# Sheet1.net
KiCad netlist of a schematic drawn in Altium Designer
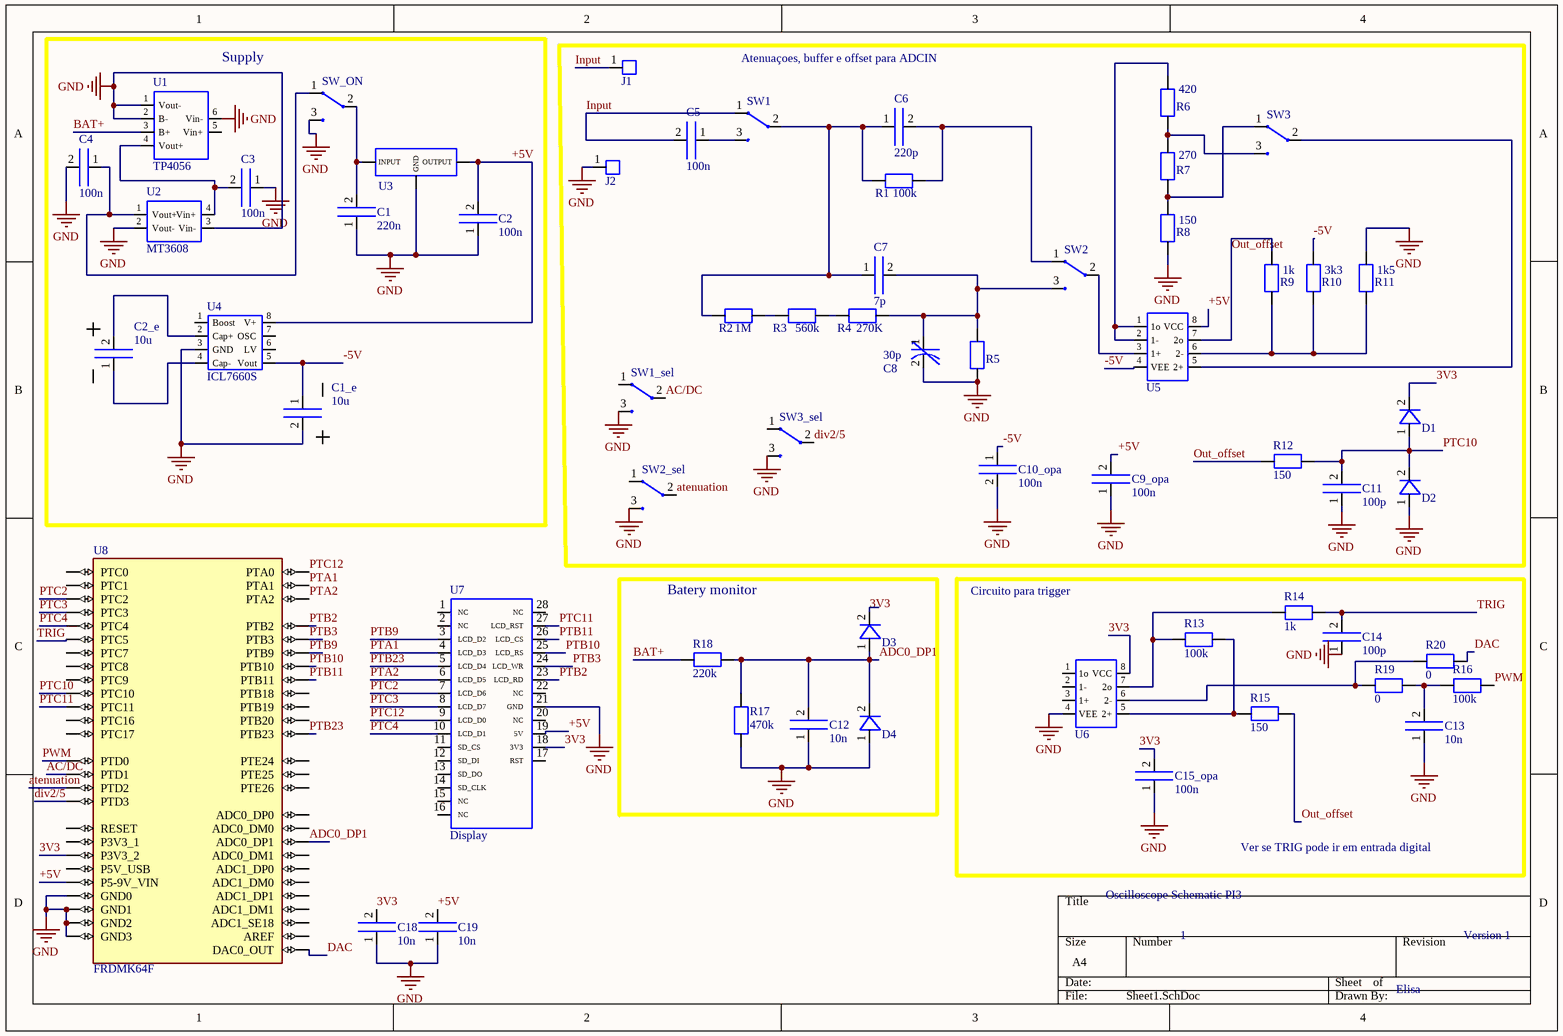
[diagram p0: Sheet1.SchDoc]

(export (version "E")
  (design (tool "Eeschema 10.0.6"))
  (components
    (comp (ref "C1")
      (value "220n")
      (footprint "0805_CAPACITOR")
      (libsource (lib "Schlib2") (part "Capacitor_0805"))
    )
    (comp (ref "C1_e")
      (value "10u")
      (footprint "CAP_THT")
      (description "CAP ALUM 47UF 20% 25V RADIAL TH")
      (libsource (lib "Schlib2") (part "EEU-FC1E470"))
    )
    (comp (ref "C2")
      (value "100n")
      (footprint "0805_CAPACITOR")
      (libsource (lib "Schlib2") (part "Capacitor_0805"))
    )
    (comp (ref "C2_e")
      (value "10u")
      (footprint "CAP_THT")
      (description "CAP ALUM 47UF 20% 25V RADIAL TH")
      (libsource (lib "Schlib2") (part "EEU-FC1E470"))
    )
    (comp (ref "C3")
      (value "100n")
      (footprint "0805_CAPACITOR")
      (libsource (lib "Schlib2") (part "Capacitor_0805"))
    )
    (comp (ref "C4")
      (value "100n")
      (footprint "0805_CAPACITOR")
      (libsource (lib "Schlib2") (part "Capacitor_0805"))
    )
    (comp (ref "C5")
      (value "100n")
      (footprint "0805_CAPACITOR")
      (libsource (lib "Schlib2") (part "Capacitor_0805"))
    )
    (comp (ref "C6")
      (value "220p")
      (footprint "0805_CAPACITOR")
      (libsource (lib "Schlib2") (part "Capacitor_0805"))
    )
    (comp (ref "C7")
      (value "7p")
      (footprint "0805_CAPACITOR")
      (libsource (lib "Schlib2") (part "Capacitor_0805"))
    )
    (comp (ref "C8")
      (value "30p")
      (footprint "CAP_TRIMM_THT")
      (libsource (lib "Schlib2") (part "CAP_TRIMM_THT"))
    )
    (comp (ref "C9_opa")
      (value "100n")
      (footprint "0805_CAPACITOR")
      (libsource (lib "Schlib2") (part "Capacitor_0805"))
    )
    (comp (ref "C10_opa")
      (value "100n")
      (footprint "0805_CAPACITOR")
      (libsource (lib "Schlib2") (part "Capacitor_0805"))
    )
    (comp (ref "C11")
      (value "100p")
      (footprint "0805_CAPACITOR")
      (libsource (lib "Schlib2") (part "Capacitor_0805"))
    )
    (comp (ref "C12")
      (value "10n")
      (footprint "0805_CAPACITOR")
      (libsource (lib "Schlib2") (part "Capacitor_0805"))
    )
    (comp (ref "C13")
      (value "10n")
      (footprint "0805_CAPACITOR")
      (libsource (lib "Schlib2") (part "Capacitor_0805"))
    )
    (comp (ref "C14")
      (value "100p")
      (footprint "0805_CAPACITOR")
      (libsource (lib "Schlib2") (part "Capacitor_0805"))
    )
    (comp (ref "C15_opa")
      (value "100n")
      (footprint "0805_CAPACITOR")
      (libsource (lib "Schlib2") (part "Capacitor_0805"))
    )
    (comp (ref "C18")
      (value "10n")
      (footprint "0805_CAPACITOR")
      (libsource (lib "Schlib2") (part "Capacitor_0805"))
    )
    (comp (ref "C19")
      (value "10n")
      (footprint "0805_CAPACITOR")
      (libsource (lib "Schlib2") (part "Capacitor_0805"))
    )
    (comp (ref "D1") (value "1N4148WT") (footprint "SOD-523") (libsource (lib "Schlib2") (part "1N4148WT")))
    (comp (ref "D2") (value "1N4148WT") (footprint "SOD-523") (libsource (lib "Schlib2") (part "1N4148WT")))
    (comp (ref "D3") (value "1N4148WT") (footprint "SOD-523") (libsource (lib "Schlib2") (part "1N4148WT")))
    (comp (ref "D4") (value "1N4148WT") (footprint "SOD-523") (libsource (lib "Schlib2") (part "1N4148WT")))
    (comp (ref "J1")
      (value "Banana_conector")
      (footprint "Banana_bourne_RED")
      (libsource (lib "Schlib2") (part "Banana_conector"))
    )
    (comp (ref "J2")
      (value "Banana_conector")
      (footprint "Banana_bourne_BLACK")
      (libsource (lib "Schlib2") (part "Banana_conector"))
    )
    (comp (ref "R1")
      (value "100k")
      (footprint "0805_RESISTOR")
      (libsource (lib "Schlib2") (part "0805_resistor"))
    )
    (comp (ref "R2")
      (value "1M")
      (footprint "0805_RESISTOR")
      (libsource (lib "Schlib2") (part "0805_resistor"))
    )
    (comp (ref "R3")
      (value "560k")
      (footprint "0805_RESISTOR")
      (libsource (lib "Schlib2") (part "0805_resistor"))
    )
    (comp (ref "R4")
      (value "270K")
      (footprint "0805_RESISTOR")
      (libsource (lib "Schlib2") (part "0805_resistor"))
    )
    (comp (ref "R5")
      (value "200k")
      (footprint "0805_RESISTOR")
      (libsource (lib "Schlib2") (part "0805_resistor"))
    )
    (comp (ref "R6")
      (value "420")
      (footprint "0805_RESISTOR")
      (libsource (lib "Schlib2") (part "0805_resistor"))
    )
    (comp (ref "R7")
      (value "270")
      (footprint "0805_RESISTOR")
      (libsource (lib "Schlib2") (part "0805_resistor"))
    )
    (comp (ref "R8")
      (value "150")
      (footprint "0805_RESISTOR")
      (libsource (lib "Schlib2") (part "0805_resistor"))
    )
    (comp (ref "R9")
      (value "1k")
      (footprint "0805_RESISTOR")
      (libsource (lib "Schlib2") (part "0805_resistor"))
    )
    (comp (ref "R10")
      (value "3k3")
      (footprint "0805_RESISTOR")
      (libsource (lib "Schlib2") (part "0805_resistor"))
    )
    (comp (ref "R11")
      (value "1k5")
      (footprint "0805_RESISTOR")
      (libsource (lib "Schlib2") (part "0805_resistor"))
    )
    (comp (ref "R12")
      (value "150")
      (footprint "0805_RESISTOR")
      (libsource (lib "Schlib2") (part "0805_resistor"))
    )
    (comp (ref "R13")
      (value "100k")
      (footprint "0805_RESISTOR")
      (libsource (lib "Schlib2") (part "0805_resistor"))
    )
    (comp (ref "R14")
      (value "1k")
      (footprint "0805_RESISTOR")
      (libsource (lib "Schlib2") (part "0805_resistor"))
    )
    (comp (ref "R15")
      (value "150")
      (footprint "0805_RESISTOR")
      (libsource (lib "Schlib2") (part "0805_resistor"))
    )
    (comp (ref "R16")
      (value "100k")
      (footprint "0805_RESISTOR")
      (libsource (lib "Schlib2") (part "0805_resistor"))
    )
    (comp (ref "R17")
      (value "470k")
      (footprint "0805_RESISTOR")
      (libsource (lib "Schlib2") (part "0805_resistor"))
    )
    (comp (ref "R18")
      (value "220k")
      (footprint "0805_RESISTOR")
      (libsource (lib "Schlib2") (part "0805_resistor"))
    )
    (comp (ref "R19")
      (value "0")
      (footprint "0805_RESISTOR")
      (libsource (lib "Schlib2") (part "0805_resistor"))
    )
    (comp (ref "R20")
      (value "0")
      (footprint "0805_RESISTOR")
      (libsource (lib "Schlib2") (part "0805_resistor"))
    )
    (comp (ref "SW1") (value "SW") (footprint "SW") (libsource (lib "Schlib2") (part "SW")))
    (comp (ref "SW1_sel") (value "SW") (footprint "SW") (libsource (lib "Schlib2") (part "SW")))
    (comp (ref "SW2") (value "SW") (footprint "SW") (libsource (lib "Schlib2") (part "SW")))
    (comp (ref "SW2_sel") (value "SW") (footprint "SW") (libsource (lib "Schlib2") (part "SW")))
    (comp (ref "SW3") (value "SW") (footprint "SW") (libsource (lib "Schlib2") (part "SW")))
    (comp (ref "SW3_sel") (value "SW") (footprint "SW") (libsource (lib "Schlib2") (part "SW")))
    (comp (ref "SW_ON") (value "SW") (footprint "SW") (libsource (lib "Schlib2") (part "SW")))
    (comp (ref "U1") (value "TP4056") (footprint "TP0456") (libsource (lib "Schlib2") (part "TP4056")))
    (comp (ref "U2") (value "MT3608") (footprint "MT3608") (libsource (lib "Schlib2") (part "MT3608")))
    (comp (ref "U3")
      (value "L7805")
      (footprint "D2PAK")
      (description "IC REG LINEAR 5V 1.5A")
      (libsource (lib "Schlib2") (part "L7805"))
    )
    (comp (ref "U4") (value "ICL7660S") (footprint "8 -PDIP") (libsource (lib "Schlib2") (part "ICL7660S")))
    (comp (ref "U5") (value "TL082C") (footprint "8-SOIC") (libsource (lib "Schlib2") (part "TL082C")))
    (comp (ref "U6") (value "TL082C") (footprint "8-SOIC") (libsource (lib "Schlib2") (part "TL082C")))
    (comp (ref "U7") (value "Display") (footprint "Display") (libsource (lib "Schlib2") (part "Display")))
    (comp (ref "U8") (value "FRDMK64F") (footprint "FRDMK64F") (libsource (lib "Schlib2") (part "FRDMK64F")))
  )
  (nets
    (net (code "1") (name "/+5V") (class "Default")
      (node (ref "C19") (pin "2") (pinfunction "0_2") (pintype "passive"))
      (node (ref "C2") (pin "2") (pinfunction "0_2") (pintype "passive"))
      (node (ref "C9_opa") (pin "2") (pinfunction "0_2") (pintype "passive"))
      (node (ref "U3") (pin "2") (pinfunction "OUTPUT_2") (pintype "passive"))
      (node (ref "U4") (pin "8") (pinfunction "V+_8") (pintype "passive"))
      (node (ref "U5") (pin "8") (pinfunction "VCC_8") (pintype "passive"))
      (node (ref "U7") (pin "19") (pinfunction "5V_19") (pintype "passive"))
      (node (ref "U8") (pin "J3-16") (pinfunction "P5-9V_VIN_J3-16") (pintype "bidirectional"))
    )
    (net (code "2") (name "/-5V") (class "Default")
      (node (ref "C10_opa") (pin "1") (pinfunction "1_1") (pintype "passive"))
      (node (ref "C1_e") (pin "1") (pinfunction "1_1") (pintype "passive"))
      (node (ref "R10") (pin "2") (pinfunction "2_2") (pintype "passive"))
      (node (ref "U4") (pin "5") (pinfunction "Vout_5") (pintype "passive"))
      (node (ref "U5") (pin "4") (pinfunction "VEE_4") (pintype "passive"))
    )
    (net (code "3") (name "/3V3") (class "Default")
      (node (ref "C15_opa") (pin "2") (pinfunction "0_2") (pintype "passive"))
      (node (ref "C18") (pin "2") (pinfunction "0_2") (pintype "passive"))
      (node (ref "D1") (pin "2") (pintype "passive"))
      (node (ref "D3") (pin "2") (pintype "passive"))
      (node (ref "U6") (pin "8") (pinfunction "VCC_8") (pintype "passive"))
      (node (ref "U7") (pin "18") (pinfunction "3V3_18") (pintype "passive"))
      (node (ref "U8") (pin "J3-8") (pinfunction "P3V3_2_J3-8") (pintype "bidirectional"))
    )
    (net (code "4") (name "/AC{slash}DC") (class "Default")
      (node (ref "SW1_sel") (pin "2") (pinfunction "2_2") (pintype "passive"))
      (node (ref "U8") (pin "J2-12") (pinfunction "PTD1_J2-12") (pintype "bidirectional"))
    )
    (net (code "5") (name "/ADC0_DP1") (class "Default")
      (node (ref "C12") (pin "2") (pinfunction "0_2") (pintype "passive"))
      (node (ref "D3") (pin "1") (pintype "passive"))
      (node (ref "D4") (pin "2") (pintype "passive"))
      (node (ref "R17") (pin "1") (pinfunction "1_1") (pintype "passive"))
      (node (ref "R18") (pin "1") (pinfunction "1_1") (pintype "passive"))
      (node (ref "U8") (pin "J4-1") (pinfunction "ADC0_DP1_J4-1") (pintype "bidirectional"))
    )
    (net (code "6") (name "/BAT+") (class "Default")
      (node (ref "R18") (pin "2") (pinfunction "2_2") (pintype "passive"))
      (node (ref "U1") (pin "3") (pinfunction "B+_3") (pintype "passive"))
    )
    (net (code "7") (name "/DAC") (class "Default")
      (node (ref "R20") (pin "1") (pinfunction "1_1") (pintype "passive"))
      (node (ref "U8") (pin "J4-11") (pinfunction "DAC0_OUT_J4-11") (pintype "bidirectional"))
    )
    (net (code "8") (name "/Input") (class "Default")
      (node (ref "C5") (pin "2") (pinfunction "0_2") (pintype "passive"))
      (node (ref "J1") (pin "1") (pinfunction "1_1") (pintype "passive"))
      (node (ref "SW1") (pin "1") (pinfunction "1_1") (pintype "passive"))
    )
    (net (code "9") (name "/Out_offset") (class "Default")
      (node (ref "R12") (pin "2") (pinfunction "2_2") (pintype "passive"))
      (node (ref "R15") (pin "1") (pinfunction "1_1") (pintype "passive"))
      (node (ref "R9") (pin "2") (pinfunction "2_2") (pintype "passive"))
      (node (ref "U5") (pin "7") (pinfunction "2o_7") (pintype "passive"))
    )
    (net (code "10") (name "/PTA1") (class "Default")
      (node (ref "U7") (pin "4") (pinfunction "LCD_D3_4") (pintype "passive"))
      (node (ref "U8") (pin "J1-8") (pinfunction "PTA1_J1-8") (pintype "bidirectional"))
    )
    (net (code "11") (name "/PTA2") (class "Default")
      (node (ref "U7") (pin "6") (pinfunction "LCD_D5_6") (pintype "passive"))
      (node (ref "U8") (pin "J1-12") (pinfunction "PTA2_J1-12") (pintype "bidirectional"))
    )
    (net (code "12") (name "/PTB2") (class "Default")
      (node (ref "U7") (pin "23") (pinfunction "LCD_RD_23") (pintype "passive"))
      (node (ref "U8") (pin "J4-2") (pinfunction "PTB2_J4-2") (pintype "bidirectional"))
    )
    (net (code "13") (name "/PTB3") (class "Default")
      (node (ref "U7") (pin "24") (pinfunction "LCD_WR_24") (pintype "passive"))
      (node (ref "U8") (pin "J4-4") (pinfunction "PTB3_J4-4") (pintype "bidirectional"))
    )
    (net (code "14") (name "/PTB9") (class "Default")
      (node (ref "U7") (pin "3") (pinfunction "LCD_D2_3") (pintype "passive"))
      (node (ref "U8") (pin "J1-6") (pinfunction "PTB9_J1-6") (pintype "bidirectional"))
    )
    (net (code "15") (name "/PTB10") (class "Default")
      (node (ref "U7") (pin "25") (pinfunction "LCD_RS_25") (pintype "passive"))
      (node (ref "U8") (pin "J4-6") (pinfunction "PTB10_J4-6") (pintype "bidirectional"))
    )
    (net (code "16") (name "/PTB11") (class "Default")
      (node (ref "U7") (pin "26") (pinfunction "LCD_CS_26") (pintype "passive"))
      (node (ref "U8") (pin "J4-8") (pinfunction "PTB11_J4-8") (pintype "bidirectional"))
    )
    (net (code "17") (name "/PTB23") (class "Default")
      (node (ref "U7") (pin "5") (pinfunction "LCD_D4_5") (pintype "passive"))
      (node (ref "U8") (pin "J1-10") (pinfunction "PTB23_J1-10") (pintype "bidirectional"))
    )
    (net (code "18") (name "/PTC2") (class "Default")
      (node (ref "U7") (pin "7") (pinfunction "LCD_D6_7") (pintype "passive"))
      (node (ref "U8") (pin "J1-14") (pinfunction "PTC2_J1-14") (pintype "bidirectional"))
    )
    (net (code "19") (name "/PTC3") (class "Default")
      (node (ref "U7") (pin "8") (pinfunction "LCD_D7_8") (pintype "passive"))
      (node (ref "U8") (pin "J1-16") (pinfunction "PTC3_J1-16") (pintype "bidirectional"))
    )
    (net (code "20") (name "/PTC4") (class "Default")
      (node (ref "U7") (pin "10") (pinfunction "LCD_D1_10") (pintype "passive"))
      (node (ref "U8") (pin "J2-4") (pinfunction "PTC4_J2-4") (pintype "bidirectional"))
    )
    (net (code "21") (name "/PTC10") (class "Default")
      (node (ref "C11") (pin "2") (pinfunction "0_2") (pintype "passive"))
      (node (ref "D1") (pin "1") (pintype "passive"))
      (node (ref "D2") (pin "2") (pintype "passive"))
      (node (ref "R12") (pin "1") (pinfunction "1_1") (pintype "passive"))
      (node (ref "U8") (pin "J4-12") (pinfunction "PTC10_J4-12") (pintype "bidirectional"))
    )
    (net (code "22") (name "/PTC11") (class "Default")
      (node (ref "U7") (pin "27") (pinfunction "LCD_RST_27") (pintype "passive"))
      (node (ref "U8") (pin "J4-10") (pinfunction "PTC11_J4-10") (pintype "bidirectional"))
    )
    (net (code "23") (name "/PTC12") (class "Default")
      (node (ref "U7") (pin "9") (pinfunction "LCD_D0_9") (pintype "passive"))
      (node (ref "U8") (pin "J2-2") (pinfunction "PTA0_J2-2") (pintype "bidirectional"))
    )
    (net (code "24") (name "/PWM") (class "Default")
      (node (ref "R16") (pin "1") (pinfunction "1_1") (pintype "passive"))
      (node (ref "U8") (pin "J2-6") (pinfunction "PTD0_J2-6") (pintype "bidirectional"))
    )
    (net (code "25") (name "/TRIG") (class "Default")
      (node (ref "C14") (pin "2") (pinfunction "0_2") (pintype "passive"))
      (node (ref "R14") (pin "1") (pinfunction "1_1") (pintype "passive"))
      (node (ref "U8") (pin "J1-15") (pinfunction "PTC5_J1-15") (pintype "bidirectional"))
    )
    (net (code "26") (name "/atenuation") (class "Default")
      (node (ref "SW2_sel") (pin "2") (pinfunction "2_2") (pintype "passive"))
      (node (ref "U8") (pin "J2-8") (pinfunction "PTD2_J2-8") (pintype "bidirectional"))
    )
    (net (code "27") (name "/div2{slash}5") (class "Default")
      (node (ref "SW3_sel") (pin "2") (pinfunction "2_2") (pintype "passive"))
      (node (ref "U8") (pin "J2-10") (pinfunction "PTD3_J2-10") (pintype "bidirectional"))
    )
    (net (code "28") (name "GND") (class "Default")
      (node (ref "C1") (pin "1") (pinfunction "1_1") (pintype "passive"))
      (node (ref "C10_opa") (pin "2") (pinfunction "0_2") (pintype "passive"))
      (node (ref "C11") (pin "1") (pinfunction "1_1") (pintype "passive"))
      (node (ref "C12") (pin "1") (pinfunction "1_1") (pintype "passive"))
      (node (ref "C13") (pin "1") (pinfunction "1_1") (pintype "passive"))
      (node (ref "C14") (pin "1") (pinfunction "1_1") (pintype "passive"))
      (node (ref "C15_opa") (pin "1") (pinfunction "1_1") (pintype "passive"))
      (node (ref "C18") (pin "1") (pinfunction "1_1") (pintype "passive"))
      (node (ref "C19") (pin "1") (pinfunction "1_1") (pintype "passive"))
      (node (ref "C1_e") (pin "2") (pinfunction "0_2") (pintype "passive"))
      (node (ref "C2") (pin "1") (pinfunction "1_1") (pintype "passive"))
      (node (ref "C3") (pin "1") (pinfunction "1_1") (pintype "passive"))
      (node (ref "C4") (pin "2") (pinfunction "0_2") (pintype "passive"))
      (node (ref "C8") (pin "2") (pinfunction "0_2") (pintype "passive"))
      (node (ref "C9_opa") (pin "1") (pinfunction "1_1") (pintype "passive"))
      (node (ref "D2") (pin "1") (pintype "passive"))
      (node (ref "D4") (pin "1") (pintype "passive"))
      (node (ref "J2") (pin "1") (pinfunction "1_1") (pintype "passive"))
      (node (ref "R11") (pin "2") (pinfunction "2_2") (pintype "passive"))
      (node (ref "R17") (pin "2") (pinfunction "2_2") (pintype "passive"))
      (node (ref "R5") (pin "1") (pinfunction "1_1") (pintype "passive"))
      (node (ref "R8") (pin "1") (pinfunction "1_1") (pintype "passive"))
      (node (ref "SW1_sel") (pin "3") (pinfunction "3_3") (pintype "passive"))
      (node (ref "SW2_sel") (pin "3") (pinfunction "3_3") (pintype "passive"))
      (node (ref "SW3_sel") (pin "3") (pinfunction "3_3") (pintype "passive"))
      (node (ref "SW_ON") (pin "3") (pinfunction "3_3") (pintype "passive"))
      (node (ref "U1") (pin "1") (pinfunction "Vout-_1") (pintype "passive"))
      (node (ref "U1") (pin "2") (pinfunction "B-_2") (pintype "passive"))
      (node (ref "U1") (pin "6") (pinfunction "Vin-_6") (pintype "passive"))
      (node (ref "U2") (pin "2") (pinfunction "Vout-_2") (pintype "passive"))
      (node (ref "U2") (pin "3") (pinfunction "Vin-_3") (pintype "passive"))
      (node (ref "U3") (pin "1") (pinfunction "GND_1") (pintype "passive"))
      (node (ref "U4") (pin "3") (pinfunction "GND_3") (pintype "passive"))
      (node (ref "U6") (pin "4") (pinfunction "VEE_4") (pintype "passive"))
      (node (ref "U7") (pin "21") (pinfunction "GND_21") (pintype "passive"))
      (node (ref "U8") (pin "J2-14") (pinfunction "GND1_J2-14") (pintype "bidirectional"))
      (node (ref "U8") (pin "J2-3") (pinfunction "GND0_J2-3") (pintype "bidirectional"))
      (node (ref "U8") (pin "J3-12") (pinfunction "GND2_J3-12") (pintype "bidirectional"))
      (node (ref "U8") (pin "J3-14") (pinfunction "GND3_J3-14") (pintype "bidirectional"))
    )
    (net (code "29") (name "Net-(C1-0)") (class "Default")
      (node (ref "C1") (pin "2") (pinfunction "0_2") (pintype "passive"))
      (node (ref "SW_ON") (pin "2") (pinfunction "2_2") (pintype "passive"))
      (node (ref "U3") (pin "3") (pinfunction "INPUT_3") (pintype "passive"))
    )
    (net (code "30") (name "Net-(C2_e-0)") (class "Default")
      (node (ref "C2_e") (pin "2") (pinfunction "0_2") (pintype "passive"))
      (node (ref "U4") (pin "2") (pinfunction "Cap+_2") (pintype "passive"))
    )
    (net (code "31") (name "Net-(C3-0)") (class "Default")
      (node (ref "C3") (pin "2") (pinfunction "0_2") (pintype "passive"))
      (node (ref "U1") (pin "4") (pinfunction "Vout+_4") (pintype "passive"))
      (node (ref "U2") (pin "4") (pinfunction "Vin+_4") (pintype "passive"))
    )
    (net (code "32") (name "Net-(C5-Pad1)") (class "Default")
      (node (ref "C5") (pin "1") (pinfunction "1_1") (pintype "passive"))
      (node (ref "SW1") (pin "3") (pinfunction "3_3") (pintype "passive"))
    )
    (net (code "33") (name "Net-(C6-0)") (class "Default")
      (node (ref "C6") (pin "2") (pinfunction "0_2") (pintype "passive"))
      (node (ref "R1") (pin "2") (pinfunction "2_2") (pintype "passive"))
      (node (ref "SW2") (pin "1") (pinfunction "1_1") (pintype "passive"))
    )
    (net (code "34") (name "Net-(C6-Pad1)") (class "Default")
      (node (ref "C6") (pin "1") (pinfunction "1_1") (pintype "passive"))
      (node (ref "C7") (pin "1") (pinfunction "1_1") (pintype "passive"))
      (node (ref "R1") (pin "1") (pinfunction "1_1") (pintype "passive"))
      (node (ref "R2") (pin "1") (pinfunction "1_1") (pintype "passive"))
      (node (ref "SW1") (pin "2") (pinfunction "2_2") (pintype "passive"))
    )
    (net (code "35") (name "Net-(C7-0)") (class "Default")
      (node (ref "C7") (pin "2") (pinfunction "0_2") (pintype "passive"))
      (node (ref "C8") (pin "1") (pinfunction "1_1") (pintype "passive"))
      (node (ref "R4") (pin "2") (pinfunction "2_2") (pintype "passive"))
      (node (ref "R5") (pin "2") (pinfunction "2_2") (pintype "passive"))
      (node (ref "SW2") (pin "3") (pinfunction "3_3") (pintype "passive"))
    )
    (net (code "36") (name "Net-(C13-0)") (class "Default")
      (node (ref "C13") (pin "2") (pinfunction "0_2") (pintype "passive"))
      (node (ref "R16") (pin "2") (pinfunction "2_2") (pintype "passive"))
      (node (ref "R19") (pin "1") (pinfunction "1_1") (pintype "passive"))
    )
    (net (code "37") (name "Net-(R2-Pad2)") (class "Default")
      (node (ref "R2") (pin "2") (pinfunction "2_2") (pintype "passive"))
      (node (ref "R3") (pin "1") (pinfunction "1_1") (pintype "passive"))
    )
    (net (code "38") (name "Net-(R3-Pad2)") (class "Default")
      (node (ref "R3") (pin "2") (pinfunction "2_2") (pintype "passive"))
      (node (ref "R4") (pin "1") (pinfunction "1_1") (pintype "passive"))
    )
    (net (code "39") (name "Net-(R6-Pad1)") (class "Default")
      (node (ref "R6") (pin "1") (pinfunction "1_1") (pintype "passive"))
      (node (ref "R7") (pin "2") (pinfunction "2_2") (pintype "passive"))
      (node (ref "SW3") (pin "3") (pinfunction "3_3") (pintype "passive"))
    )
    (net (code "40") (name "Net-(R7-Pad1)") (class "Default")
      (node (ref "R7") (pin "1") (pinfunction "1_1") (pintype "passive"))
      (node (ref "R8") (pin "2") (pinfunction "2_2") (pintype "passive"))
      (node (ref "SW3") (pin "1") (pinfunction "1_1") (pintype "passive"))
    )
    (net (code "41") (name "Net-(U2-Vout+)") (class "Default")
      (node (ref "C4") (pin "1") (pinfunction "1_1") (pintype "passive"))
      (node (ref "SW_ON") (pin "1") (pinfunction "1_1") (pintype "passive"))
      (node (ref "U2") (pin "1") (pinfunction "Vout+_1") (pintype "passive"))
    )
    (net (code "42") (name "Net-(U4-Cap-)") (class "Default")
      (node (ref "C2_e") (pin "1") (pinfunction "1_1") (pintype "passive"))
      (node (ref "U4") (pin "4") (pinfunction "Cap-_4") (pintype "passive"))
    )
    (net (code "43") (name "Net-(U5-1+)") (class "Default")
      (node (ref "SW2") (pin "2") (pinfunction "2_2") (pintype "passive"))
      (node (ref "U5") (pin "3") (pinfunction "1+_3") (pintype "passive"))
    )
    (net (code "44") (name "Net-(U5-1-)") (class "Default")
      (node (ref "R6") (pin "2") (pinfunction "2_2") (pintype "passive"))
      (node (ref "U5") (pin "1") (pinfunction "1o_1") (pintype "passive"))
      (node (ref "U5") (pin "2") (pinfunction "1-_2") (pintype "passive"))
    )
    (net (code "45") (name "Net-(U5-2+)") (class "Default")
      (node (ref "SW3") (pin "2") (pinfunction "2_2") (pintype "passive"))
      (node (ref "U5") (pin "5") (pinfunction "2+_5") (pintype "passive"))
    )
    (net (code "46") (name "Net-(U5-2-)") (class "Default")
      (node (ref "R10") (pin "1") (pinfunction "1_1") (pintype "passive"))
      (node (ref "R11") (pin "1") (pinfunction "1_1") (pintype "passive"))
      (node (ref "R9") (pin "1") (pinfunction "1_1") (pintype "passive"))
      (node (ref "U5") (pin "6") (pinfunction "2-_6") (pintype "passive"))
    )
    (net (code "47") (name "Net-(U6-2+)") (class "Default")
      (node (ref "R13") (pin "1") (pinfunction "1_1") (pintype "passive"))
      (node (ref "R15") (pin "2") (pinfunction "2_2") (pintype "passive"))
      (node (ref "U6") (pin "5") (pinfunction "2+_5") (pintype "passive"))
    )
    (net (code "48") (name "Net-(U6-2-)") (class "Default")
      (node (ref "R19") (pin "2") (pinfunction "2_2") (pintype "passive"))
      (node (ref "R20") (pin "2") (pinfunction "2_2") (pintype "passive"))
      (node (ref "U6") (pin "6") (pinfunction "2-_6") (pintype "passive"))
    )
    (net (code "49") (name "Net-(U6-2o)") (class "Default")
      (node (ref "R13") (pin "2") (pinfunction "2_2") (pintype "passive"))
      (node (ref "R14") (pin "2") (pinfunction "2_2") (pintype "passive"))
      (node (ref "U6") (pin "7") (pinfunction "2o_7") (pintype "passive"))
    )
    (net (code "50") (name "unconnected-(SW1_sel-Pad1)") (class "Default")
      (node (ref "SW1_sel") (pin "1") (pinfunction "1_1") (pintype "passive"))
    )
    (net (code "51") (name "unconnected-(SW2_sel-Pad1)") (class "Default")
      (node (ref "SW2_sel") (pin "1") (pinfunction "1_1") (pintype "passive"))
    )
    (net (code "52") (name "unconnected-(SW3_sel-Pad1)") (class "Default")
      (node (ref "SW3_sel") (pin "1") (pinfunction "1_1") (pintype "passive"))
    )
    (net (code "53") (name "unconnected-(U1-Vin+-Pad5)") (class "Default")
      (node (ref "U1") (pin "5") (pinfunction "Vin+_5") (pintype "passive"))
    )
    (net (code "54") (name "unconnected-(U4-Boost-Pad1)") (class "Default")
      (node (ref "U4") (pin "1") (pinfunction "Boost_1") (pintype "passive"))
    )
    (net (code "55") (name "unconnected-(U4-LV-Pad6)") (class "Default")
      (node (ref "U4") (pin "6") (pinfunction "LV_6") (pintype "passive"))
    )
    (net (code "56") (name "unconnected-(U4-OSC-Pad7)") (class "Default")
      (node (ref "U4") (pin "7") (pinfunction "OSC_7") (pintype "passive"))
    )
    (net (code "57") (name "unconnected-(U6-1+-Pad3)") (class "Default")
      (node (ref "U6") (pin "3") (pinfunction "1+_3") (pintype "passive"))
    )
    (net (code "58") (name "unconnected-(U6-1--Pad2)") (class "Default")
      (node (ref "U6") (pin "2") (pinfunction "1-_2") (pintype "passive"))
    )
    (net (code "59") (name "unconnected-(U6-1o-Pad1)") (class "Default")
      (node (ref "U6") (pin "1") (pinfunction "1o_1") (pintype "passive"))
    )
    (net (code "60") (name "unconnected-(U7-NC-Pad1)") (class "Default")
      (node (ref "U7") (pin "1") (pinfunction "NC_1") (pintype "passive"))
    )
    (net (code "61") (name "unconnected-(U7-NC-Pad2)") (class "Default")
      (node (ref "U7") (pin "2") (pinfunction "NC_2") (pintype "passive"))
    )
    (net (code "62") (name "unconnected-(U7-NC-Pad15)") (class "Default")
      (node (ref "U7") (pin "15") (pinfunction "NC_15") (pintype "passive"))
    )
    (net (code "63") (name "unconnected-(U7-NC-Pad16)") (class "Default")
      (node (ref "U7") (pin "16") (pinfunction "NC_16") (pintype "passive"))
    )
    (net (code "64") (name "unconnected-(U7-NC-Pad20)") (class "Default")
      (node (ref "U7") (pin "20") (pinfunction "NC_20") (pintype "passive"))
    )
    (net (code "65") (name "unconnected-(U7-NC-Pad22)") (class "Default")
      (node (ref "U7") (pin "22") (pinfunction "NC_22") (pintype "passive"))
    )
    (net (code "66") (name "unconnected-(U7-NC-Pad28)") (class "Default")
      (node (ref "U7") (pin "28") (pinfunction "NC_28") (pintype "passive"))
    )
    (net (code "67") (name "unconnected-(U7-RST-Pad17)") (class "Default")
      (node (ref "U7") (pin "17") (pinfunction "RST_17") (pintype "passive"))
    )
    (net (code "68") (name "unconnected-(U7-SD_CLK-Pad14)") (class "Default")
      (node (ref "U7") (pin "14") (pinfunction "SD_CLK_14") (pintype "passive"))
    )
    (net (code "69") (name "unconnected-(U7-SD_CS-Pad11)") (class "Default")
      (node (ref "U7") (pin "11") (pinfunction "SD_CS_11") (pintype "passive"))
    )
    (net (code "70") (name "unconnected-(U7-SD_DI-Pad12)") (class "Default")
      (node (ref "U7") (pin "12") (pinfunction "SD_DI_12") (pintype "passive"))
    )
    (net (code "71") (name "unconnected-(U7-SD_DO-Pad13)") (class "Default")
      (node (ref "U7") (pin "13") (pinfunction "SD_DO_13") (pintype "passive"))
    )
    (net (code "72") (name "unconnected-(U8-ADC0_DM0-PadJ2-7)") (class "Default")
      (node (ref "U8") (pin "J2-7") (pinfunction "ADC0_DM0_J2-7") (pintype "bidirectional"))
    )
    (net (code "73") (name "unconnected-(U8-ADC0_DM1-PadJ4-3)") (class "Default")
      (node (ref "U8") (pin "J4-3") (pinfunction "ADC0_DM1_J4-3") (pintype "bidirectional"))
    )
    (net (code "74") (name "unconnected-(U8-ADC0_DP0-PadJ2-5)") (class "Default")
      (node (ref "U8") (pin "J2-5") (pinfunction "ADC0_DP0_J2-5") (pintype "bidirectional"))
    )
    (net (code "75") (name "unconnected-(U8-ADC1_DM0-PadJ2-13)") (class "Default")
      (node (ref "U8") (pin "J2-13") (pinfunction "ADC1_DM0_J2-13") (pintype "bidirectional"))
    )
    (net (code "76") (name "unconnected-(U8-ADC1_DM1-PadJ4-7)") (class "Default")
      (node (ref "U8") (pin "J4-7") (pinfunction "ADC1_DM1_J4-7") (pintype "bidirectional"))
    )
    (net (code "77") (name "unconnected-(U8-ADC1_DP0-PadJ2-11)") (class "Default")
      (node (ref "U8") (pin "J2-11") (pinfunction "ADC1_DP0_J2-11") (pintype "bidirectional"))
    )
    (net (code "78") (name "unconnected-(U8-ADC1_DP1-PadJ4-5)") (class "Default")
      (node (ref "U8") (pin "J4-5") (pinfunction "ADC1_DP1_J4-5") (pintype "bidirectional"))
    )
    (net (code "79") (name "unconnected-(U8-ADC1_SE18-PadJ2-17)") (class "Default")
      (node (ref "U8") (pin "J2-17") (pinfunction "ADC1_SE18_J2-17") (pintype "bidirectional"))
    )
    (net (code "80") (name "unconnected-(U8-AREF-PadJ2-16)") (class "Default")
      (node (ref "U8") (pin "J2-16") (pinfunction "AREF_J2-16") (pintype "bidirectional"))
    )
    (net (code "81") (name "unconnected-(U8-P3V3_1-PadJ3-4)") (class "Default")
      (node (ref "U8") (pin "J3-4") (pinfunction "P3V3_1_J3-4") (pintype "bidirectional"))
    )
    (net (code "82") (name "unconnected-(U8-P5V_USB-PadJ3-10)") (class "Default")
      (node (ref "U8") (pin "J3-10") (pinfunction "P5V_USB_J3-10") (pintype "bidirectional"))
    )
    (net (code "83") (name "unconnected-(U8-PTB18-PadJ1-1)") (class "Default")
      (node (ref "U8") (pin "J1-1") (pinfunction "PTB18_J1-1") (pintype "bidirectional"))
    )
    (net (code "84") (name "unconnected-(U8-PTB19-PadJ1-3)") (class "Default")
      (node (ref "U8") (pin "J1-3") (pinfunction "PTB19_J1-3") (pintype "bidirectional"))
    )
    (net (code "85") (name "unconnected-(U8-PTB20-PadJ4-9)") (class "Default")
      (node (ref "U8") (pin "J4-9") (pinfunction "PTB20_J4-9") (pintype "bidirectional"))
    )
    (net (code "86") (name "unconnected-(U8-PTC0-PadJ1-11)") (class "Default")
      (node (ref "U8") (pin "J1-11") (pinfunction "PTC0_J1-11") (pintype "bidirectional"))
    )
    (net (code "87") (name "unconnected-(U8-PTC1-PadJ1-5)") (class "Default")
      (node (ref "U8") (pin "J1-5") (pinfunction "PTC1_J1-5") (pintype "bidirectional"))
    )
    (net (code "88") (name "unconnected-(U8-PTC7-PadJ1-13)") (class "Default")
      (node (ref "U8") (pin "J1-13") (pinfunction "PTC7_J1-13") (pintype "bidirectional"))
    )
    (net (code "89") (name "unconnected-(U8-PTC8-PadJ1-7)") (class "Default")
      (node (ref "U8") (pin "J1-7") (pinfunction "PTC8_J1-7") (pintype "bidirectional"))
    )
    (net (code "90") (name "unconnected-(U8-PTC9-PadJ1-9)") (class "Default")
      (node (ref "U8") (pin "J1-9") (pinfunction "PTC9_J1-9") (pintype "bidirectional"))
    )
    (net (code "91") (name "unconnected-(U8-PTC16-PadJ1-2)") (class "Default")
      (node (ref "U8") (pin "J1-2") (pinfunction "PTC16_J1-2") (pintype "bidirectional"))
    )
    (net (code "92") (name "unconnected-(U8-PTC17-PadJ1-4)") (class "Default")
      (node (ref "U8") (pin "J1-4") (pinfunction "PTC17_J1-4") (pintype "bidirectional"))
    )
    (net (code "93") (name "unconnected-(U8-PTE24-PadJ2-20)") (class "Default")
      (node (ref "U8") (pin "J2-20") (pinfunction "PTE24_J2-20") (pintype "bidirectional"))
    )
    (net (code "94") (name "unconnected-(U8-PTE25-PadJ2-18)") (class "Default")
      (node (ref "U8") (pin "J2-18") (pinfunction "PTE25_J2-18") (pintype "bidirectional"))
    )
    (net (code "95") (name "unconnected-(U8-PTE26-PadJ2-1)") (class "Default")
      (node (ref "U8") (pin "J2-1") (pinfunction "PTE26_J2-1") (pintype "bidirectional"))
    )
    (net (code "96") (name "unconnected-(U8-RESET-PadJ3-6)") (class "Default")
      (node (ref "U8") (pin "J3-6") (pinfunction "RESET_J3-6") (pintype "bidirectional"))
    )
  )
)
